# TH555-IO.net
KiCad netlist of a schematic drawn in EAGLE
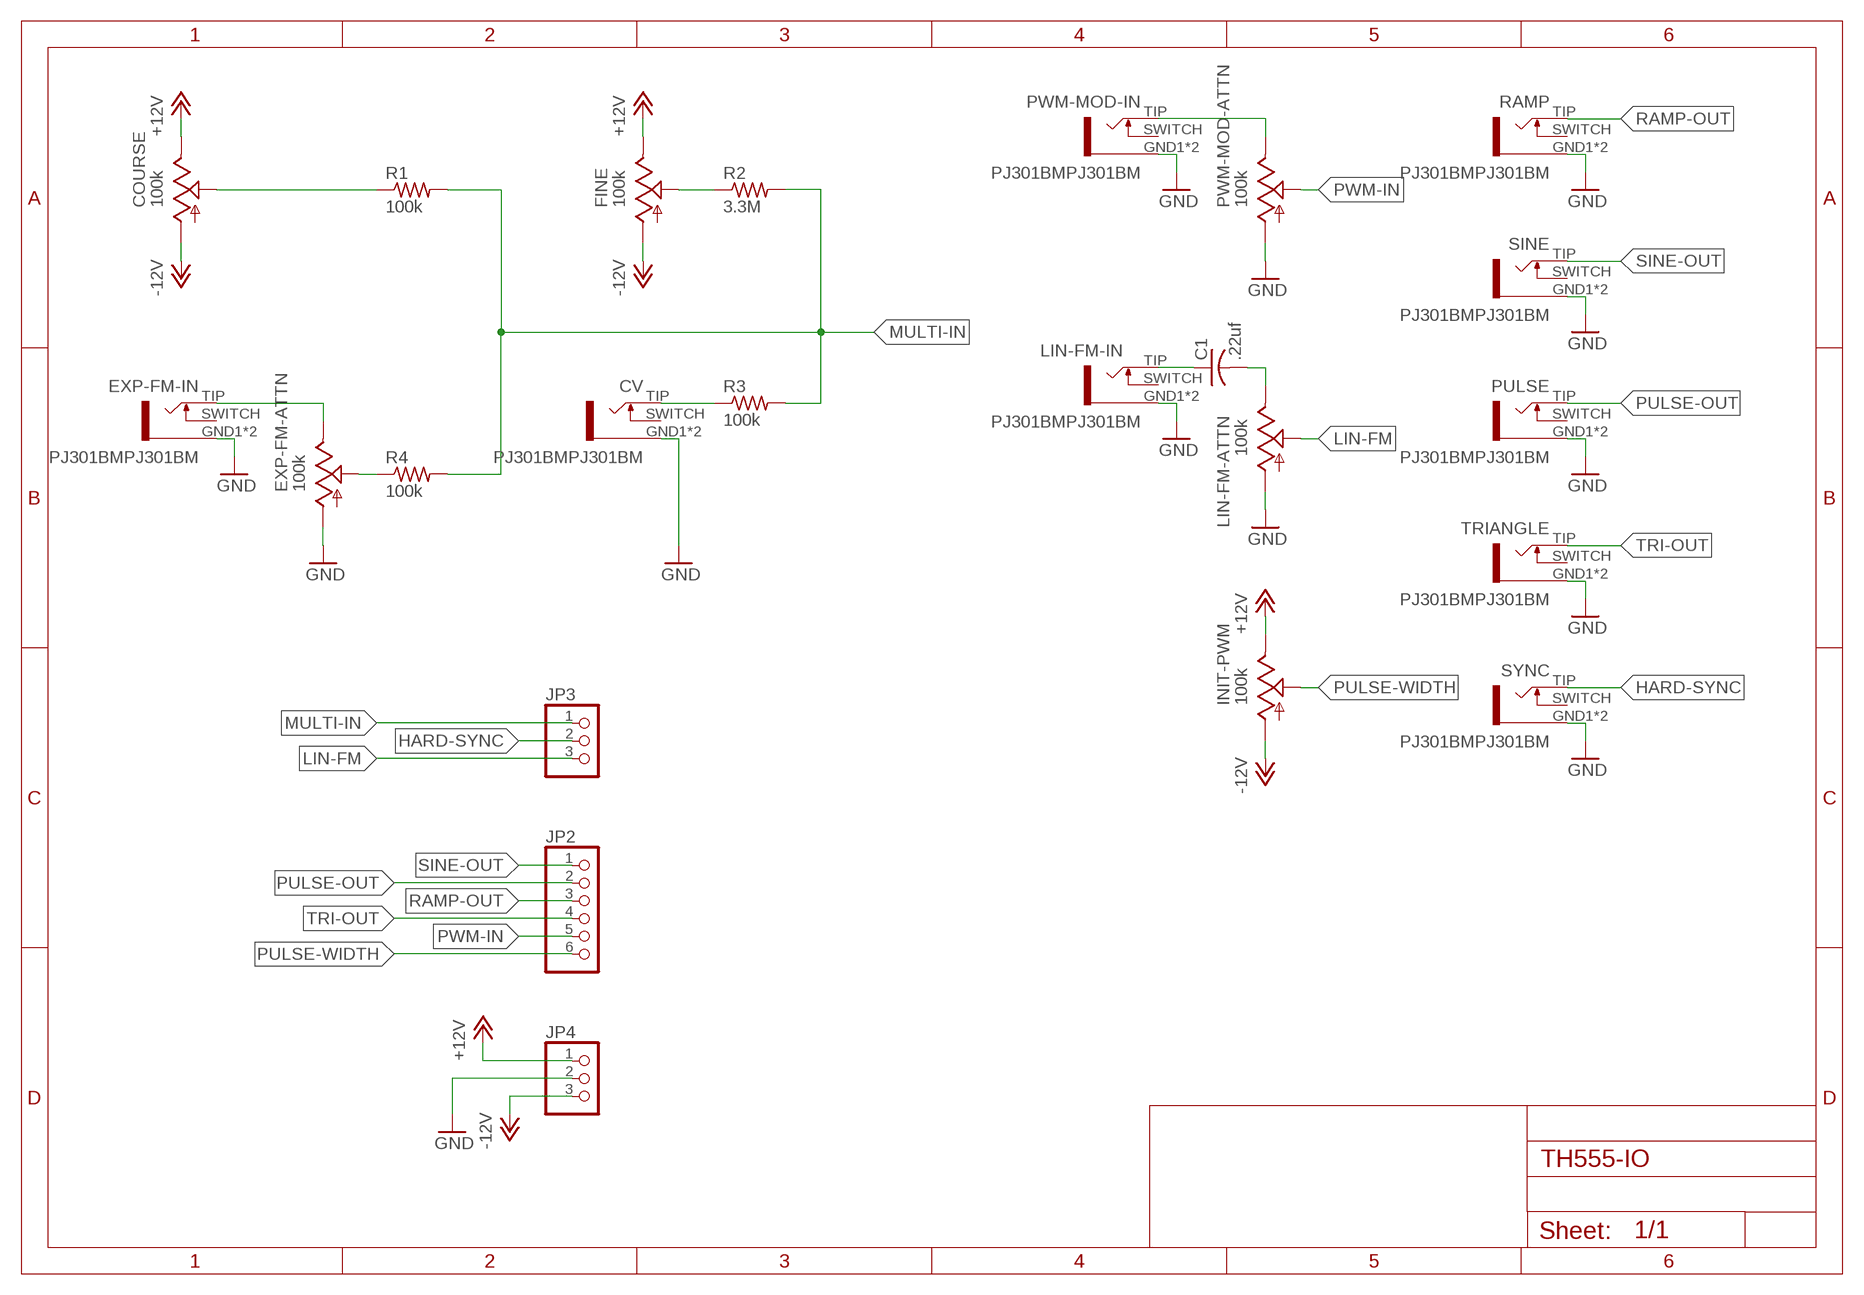
[diagram p0: schematic, sheet 1]

(export (version "E")
  (design (tool "Eeschema 10.0.6"))
  (components
    (comp (ref "C1")
      (value ".22uf")
      (footprint "eagle-import:C050-024X044")
      (libsource (lib "eagle-import") (part "C-US050-024X044"))
    )
    (comp (ref "COURSE")
      (value "100k")
      (footprint "eagle-import:EVUF")
      (libsource (lib "eagle-import") (part "ALPHA-9MMA"))
    )
    (comp (ref "CV")
      (value "PJ301BMPJ301BM")
      (footprint "eagle-import:PJ301BM")
      (libsource (lib "eagle-import") (part "PJ301BMPJ301BM"))
    )
    (comp (ref "EXP-FM-ATTN")
      (value "100k")
      (footprint "eagle-import:EVUF")
      (libsource (lib "eagle-import") (part "ALPHA-9MMA"))
    )
    (comp (ref "EXP-FM-IN")
      (value "PJ301BMPJ301BM")
      (footprint "eagle-import:PJ301BM")
      (libsource (lib "eagle-import") (part "PJ301BMPJ301BM"))
    )
    (comp (ref "FINE")
      (value "100k")
      (footprint "eagle-import:EVUF")
      (libsource (lib "eagle-import") (part "ALPHA-9MMA"))
    )
    (comp (ref "INIT-PWM")
      (value "100k")
      (footprint "eagle-import:EVUF")
      (libsource (lib "eagle-import") (part "ALPHA-9MMA"))
    )
    (comp (ref "JP2")
      (value "PINHD-1X6")
      (footprint "eagle-import:1X06")
      (libsource (lib "eagle-import") (part "PINHD-1X6"))
    )
    (comp (ref "JP3")
      (value "PINHD-1X3")
      (footprint "eagle-import:1X03")
      (libsource (lib "eagle-import") (part "PINHD-1X3"))
    )
    (comp (ref "JP4")
      (value "PINHD-1X3")
      (footprint "eagle-import:1X03")
      (libsource (lib "eagle-import") (part "PINHD-1X3"))
    )
    (comp (ref "LIN-FM-ATTN")
      (value "100k")
      (footprint "eagle-import:EVUF")
      (libsource (lib "eagle-import") (part "ALPHA-9MMA"))
    )
    (comp (ref "LIN-FM-IN")
      (value "PJ301BMPJ301BM")
      (footprint "eagle-import:PJ301BM")
      (libsource (lib "eagle-import") (part "PJ301BMPJ301BM"))
    )
    (comp (ref "PULSE")
      (value "PJ301BMPJ301BM")
      (footprint "eagle-import:PJ301BM")
      (libsource (lib "eagle-import") (part "PJ301BMPJ301BM"))
    )
    (comp (ref "PWM-MOD-ATTN")
      (value "100k")
      (footprint "eagle-import:EVUF")
      (libsource (lib "eagle-import") (part "ALPHA-9MMA"))
    )
    (comp (ref "PWM-MOD-IN")
      (value "PJ301BMPJ301BM")
      (footprint "eagle-import:PJ301BM")
      (libsource (lib "eagle-import") (part "PJ301BMPJ301BM"))
    )
    (comp (ref "R1")
      (value "100k")
      (footprint "eagle-import:0207_10")
      (libsource (lib "eagle-import") (part "R-US_0207/10"))
    )
    (comp (ref "R2")
      (value "3.3M")
      (footprint "eagle-import:0207_10")
      (libsource (lib "eagle-import") (part "R-US_0207/10"))
    )
    (comp (ref "R3")
      (value "100k")
      (footprint "eagle-import:0207_10")
      (libsource (lib "eagle-import") (part "R-US_0207/10"))
    )
    (comp (ref "R4")
      (value "100k")
      (footprint "eagle-import:0207_10")
      (libsource (lib "eagle-import") (part "R-US_0207/10"))
    )
    (comp (ref "RAMP")
      (value "PJ301BMPJ301BM")
      (footprint "eagle-import:PJ301BM")
      (libsource (lib "eagle-import") (part "PJ301BMPJ301BM"))
    )
    (comp (ref "SINE")
      (value "PJ301BMPJ301BM")
      (footprint "eagle-import:PJ301BM")
      (libsource (lib "eagle-import") (part "PJ301BMPJ301BM"))
    )
    (comp (ref "SYNC")
      (value "PJ301BMPJ301BM")
      (footprint "eagle-import:PJ301BM")
      (libsource (lib "eagle-import") (part "PJ301BMPJ301BM"))
    )
    (comp (ref "TRIANGLE")
      (value "PJ301BMPJ301BM")
      (footprint "eagle-import:PJ301BM")
      (libsource (lib "eagle-import") (part "PJ301BMPJ301BM"))
    )
  )
  (nets
    (net (code "1") (name "+12V") (class "Default")
      (node (ref "COURSE") (pin "3") (pinfunction "E_3") (pintype "passive"))
      (node (ref "FINE") (pin "3") (pinfunction "E_3") (pintype "passive"))
      (node (ref "INIT-PWM") (pin "3") (pinfunction "E_3") (pintype "passive"))
      (node (ref "JP4") (pin "1") (pinfunction "1_1") (pintype "passive"))
    )
    (net (code "2") (name "-12V") (class "Default")
      (node (ref "COURSE") (pin "1") (pinfunction "A_1") (pintype "passive"))
      (node (ref "FINE") (pin "1") (pinfunction "A_1") (pintype "passive"))
      (node (ref "INIT-PWM") (pin "1") (pinfunction "A_1") (pintype "passive"))
      (node (ref "JP4") (pin "3") (pinfunction "3_3") (pintype "passive"))
    )
    (net (code "3") (name "GND") (class "Default")
      (node (ref "CV") (pin "GND1") (pinfunction "5_GND1") (pintype "passive"))
      (node (ref "CV") (pin "GND2") (pinfunction "5_GND2") (pintype "passive"))
      (node (ref "EXP-FM-ATTN") (pin "1") (pinfunction "A_1") (pintype "passive"))
      (node (ref "EXP-FM-IN") (pin "GND1") (pinfunction "5_GND1") (pintype "passive"))
      (node (ref "EXP-FM-IN") (pin "GND2") (pinfunction "5_GND2") (pintype "passive"))
      (node (ref "JP4") (pin "2") (pinfunction "2_2") (pintype "passive"))
      (node (ref "LIN-FM-ATTN") (pin "1") (pinfunction "A_1") (pintype "passive"))
      (node (ref "LIN-FM-IN") (pin "GND1") (pinfunction "5_GND1") (pintype "passive"))
      (node (ref "LIN-FM-IN") (pin "GND2") (pinfunction "5_GND2") (pintype "passive"))
      (node (ref "PULSE") (pin "GND1") (pinfunction "5_GND1") (pintype "passive"))
      (node (ref "PULSE") (pin "GND2") (pinfunction "5_GND2") (pintype "passive"))
      (node (ref "PWM-MOD-ATTN") (pin "1") (pinfunction "A_1") (pintype "passive"))
      (node (ref "PWM-MOD-IN") (pin "GND1") (pinfunction "5_GND1") (pintype "passive"))
      (node (ref "PWM-MOD-IN") (pin "GND2") (pinfunction "5_GND2") (pintype "passive"))
      (node (ref "RAMP") (pin "GND1") (pinfunction "5_GND1") (pintype "passive"))
      (node (ref "RAMP") (pin "GND2") (pinfunction "5_GND2") (pintype "passive"))
      (node (ref "SINE") (pin "GND1") (pinfunction "5_GND1") (pintype "passive"))
      (node (ref "SINE") (pin "GND2") (pinfunction "5_GND2") (pintype "passive"))
      (node (ref "SYNC") (pin "GND1") (pinfunction "5_GND1") (pintype "passive"))
      (node (ref "SYNC") (pin "GND2") (pinfunction "5_GND2") (pintype "passive"))
      (node (ref "TRIANGLE") (pin "GND1") (pinfunction "5_GND1") (pintype "passive"))
      (node (ref "TRIANGLE") (pin "GND2") (pinfunction "5_GND2") (pintype "passive"))
    )
    (net (code "4") (name "HARD-SYNC") (class "Default")
      (node (ref "JP3") (pin "2") (pinfunction "2_2") (pintype "passive"))
      (node (ref "SYNC") (pin "TIP") (pinfunction "3_TIP") (pintype "passive"))
    )
    (net (code "5") (name "LIN-FM") (class "Default")
      (node (ref "JP3") (pin "3") (pinfunction "3_3") (pintype "passive"))
      (node (ref "LIN-FM-ATTN") (pin "2") (pinfunction "S_2") (pintype "passive"))
    )
    (net (code "6") (name "MULTI-IN") (class "Default")
      (node (ref "JP3") (pin "1") (pinfunction "1_1") (pintype "passive"))
      (node (ref "R1") (pin "2") (pinfunction "2_2") (pintype "passive"))
      (node (ref "R2") (pin "2") (pinfunction "2_2") (pintype "passive"))
      (node (ref "R3") (pin "2") (pinfunction "2_2") (pintype "passive"))
      (node (ref "R4") (pin "2") (pinfunction "2_2") (pintype "passive"))
    )
    (net (code "7") (name "Net-(COURSE-S)") (class "Default")
      (node (ref "COURSE") (pin "2") (pinfunction "S_2") (pintype "passive"))
      (node (ref "R1") (pin "1") (pinfunction "1_1") (pintype "passive"))
    )
    (net (code "8") (name "Net-(CV-3)") (class "Default")
      (node (ref "CV") (pin "TIP") (pinfunction "3_TIP") (pintype "passive"))
      (node (ref "R3") (pin "1") (pinfunction "1_1") (pintype "passive"))
    )
    (net (code "9") (name "Net-(EXP-FM-ATTN-E)") (class "Default")
      (node (ref "EXP-FM-ATTN") (pin "3") (pinfunction "E_3") (pintype "passive"))
      (node (ref "EXP-FM-IN") (pin "TIP") (pinfunction "3_TIP") (pintype "passive"))
    )
    (net (code "10") (name "Net-(EXP-FM-ATTN-S)") (class "Default")
      (node (ref "EXP-FM-ATTN") (pin "2") (pinfunction "S_2") (pintype "passive"))
      (node (ref "R4") (pin "1") (pinfunction "1_1") (pintype "passive"))
    )
    (net (code "11") (name "Net-(FINE-S)") (class "Default")
      (node (ref "FINE") (pin "2") (pinfunction "S_2") (pintype "passive"))
      (node (ref "R2") (pin "1") (pinfunction "1_1") (pintype "passive"))
    )
    (net (code "12") (name "Net-(LIN-FM-ATTN-E)") (class "Default")
      (node (ref "C1") (pin "2") (pinfunction "2_2") (pintype "passive"))
      (node (ref "LIN-FM-ATTN") (pin "3") (pinfunction "E_3") (pintype "passive"))
    )
    (net (code "13") (name "Net-(LIN-FM-IN-3)") (class "Default")
      (node (ref "C1") (pin "1") (pinfunction "1_1") (pintype "passive"))
      (node (ref "LIN-FM-IN") (pin "TIP") (pinfunction "3_TIP") (pintype "passive"))
    )
    (net (code "14") (name "Net-(PWM-MOD-ATTN-E)") (class "Default")
      (node (ref "PWM-MOD-ATTN") (pin "3") (pinfunction "E_3") (pintype "passive"))
      (node (ref "PWM-MOD-IN") (pin "TIP") (pinfunction "3_TIP") (pintype "passive"))
    )
    (net (code "15") (name "PULSE-OUT") (class "Default")
      (node (ref "JP2") (pin "2") (pinfunction "2_2") (pintype "passive"))
      (node (ref "PULSE") (pin "TIP") (pinfunction "3_TIP") (pintype "passive"))
    )
    (net (code "16") (name "PULSE-WIDTH") (class "Default")
      (node (ref "INIT-PWM") (pin "2") (pinfunction "S_2") (pintype "passive"))
      (node (ref "JP2") (pin "6") (pinfunction "6_6") (pintype "passive"))
    )
    (net (code "17") (name "PWM-IN") (class "Default")
      (node (ref "JP2") (pin "5") (pinfunction "5_5") (pintype "passive"))
      (node (ref "PWM-MOD-ATTN") (pin "2") (pinfunction "S_2") (pintype "passive"))
    )
    (net (code "18") (name "RAMP-OUT") (class "Default")
      (node (ref "JP2") (pin "3") (pinfunction "3_3") (pintype "passive"))
      (node (ref "RAMP") (pin "TIP") (pinfunction "3_TIP") (pintype "passive"))
    )
    (net (code "19") (name "SINE-OUT") (class "Default")
      (node (ref "JP2") (pin "1") (pinfunction "1_1") (pintype "passive"))
      (node (ref "SINE") (pin "TIP") (pinfunction "3_TIP") (pintype "passive"))
    )
    (net (code "20") (name "TRI-OUT") (class "Default")
      (node (ref "JP2") (pin "4") (pinfunction "4_4") (pintype "passive"))
      (node (ref "TRIANGLE") (pin "TIP") (pinfunction "3_TIP") (pintype "passive"))
    )
    (net (code "21") (name "unconnected-(CV-4-PadSWITCH)") (class "Default")
      (node (ref "CV") (pin "SWITCH") (pinfunction "4_SWITCH") (pintype "passive"))
    )
    (net (code "22") (name "unconnected-(EXP-FM-IN-4-PadSWITCH)") (class "Default")
      (node (ref "EXP-FM-IN") (pin "SWITCH") (pinfunction "4_SWITCH") (pintype "passive"))
    )
    (net (code "23") (name "unconnected-(LIN-FM-IN-4-PadSWITCH)") (class "Default")
      (node (ref "LIN-FM-IN") (pin "SWITCH") (pinfunction "4_SWITCH") (pintype "passive"))
    )
    (net (code "24") (name "unconnected-(PULSE-4-PadSWITCH)") (class "Default")
      (node (ref "PULSE") (pin "SWITCH") (pinfunction "4_SWITCH") (pintype "passive"))
    )
    (net (code "25") (name "unconnected-(PWM-MOD-IN-4-PadSWITCH)") (class "Default")
      (node (ref "PWM-MOD-IN") (pin "SWITCH") (pinfunction "4_SWITCH") (pintype "passive"))
    )
    (net (code "26") (name "unconnected-(RAMP-4-PadSWITCH)") (class "Default")
      (node (ref "RAMP") (pin "SWITCH") (pinfunction "4_SWITCH") (pintype "passive"))
    )
    (net (code "27") (name "unconnected-(SINE-4-PadSWITCH)") (class "Default")
      (node (ref "SINE") (pin "SWITCH") (pinfunction "4_SWITCH") (pintype "passive"))
    )
    (net (code "28") (name "unconnected-(SYNC-4-PadSWITCH)") (class "Default")
      (node (ref "SYNC") (pin "SWITCH") (pinfunction "4_SWITCH") (pintype "passive"))
    )
    (net (code "29") (name "unconnected-(TRIANGLE-4-PadSWITCH)") (class "Default")
      (node (ref "TRIANGLE") (pin "SWITCH") (pinfunction "4_SWITCH") (pintype "passive"))
    )
  )
)
